# UWB_DWM1000.net
KiCad netlist of a schematic drawn in Altium Designer
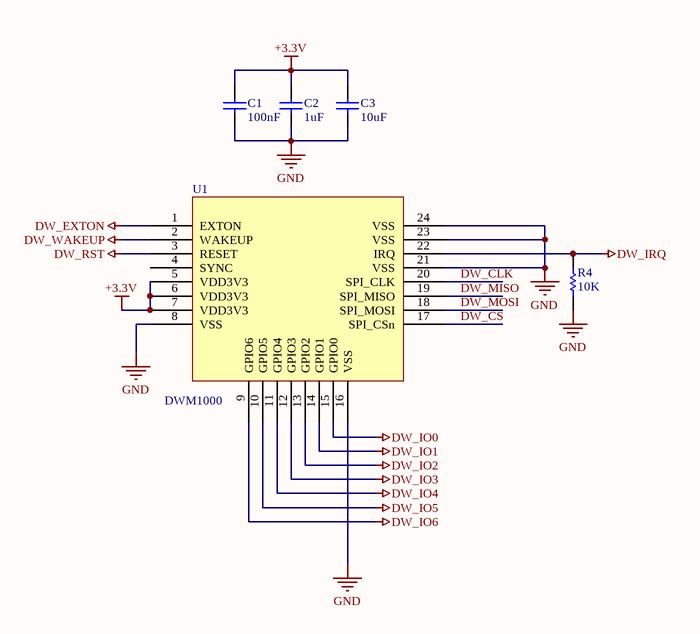
[diagram p0: UWB_DWM1000.SchDoc]

(export (version "E")
  (design (tool "Eeschema 10.0.6"))
  (components
    (comp (ref "C1")
      (value "100nF")
      (footprint "CAPC1608N")
      (description "Capacitor")
      (fields (field (name "Comment") "Cap") (field (name "PUBLISHER") "Altium Limited"))
      (libsource (lib "Leo") (part "Cap"))
    )
    (comp (ref "C2")
      (value "1uF")
      (footprint "CAPC1608N")
      (description "Capacitor")
      (fields (field (name "Comment") "Cap") (field (name "PUBLISHER") "Altium Limited"))
      (libsource (lib "Leo") (part "Cap"))
    )
    (comp (ref "C3")
      (value "10uF")
      (footprint "CAPC1608N")
      (description "Capacitor")
      (fields (field (name "Comment") "Cap") (field (name "PUBLISHER") "Altium Limited"))
      (libsource (lib "Leo") (part "Cap"))
    )
    (comp (ref "R4")
      (value "10K")
      (footprint "RESC1608N")
      (description "Resistor")
      (fields (field (name "Comment") "Res1") (field (name "PUBLISHER") "Altium Limited"))
      (libsource (lib "Leo") (part "Res1"))
    )
    (comp (ref "U1")
      (value "DWM1000")
      (footprint "DWM1000")
      (description "MOD IEEE802.15.4-2011 UWB TXRX")
      (fields (field (name "MANUFACTURER") "Decawave Limited"))
      (libsource (lib "Leo") (part "DWM1000"))
    )
  )
  (nets
    (net (code "1") (name "+3.3V") (class "Default")
      (node (ref "C1") (pin "1") (pinfunction "1_1") (pintype "passive"))
      (node (ref "C2") (pin "1") (pinfunction "1_1") (pintype "passive"))
      (node (ref "C3") (pin "1") (pinfunction "1_1") (pintype "passive"))
      (node (ref "U1") (pin "5") (pinfunction "VDD3V3_5") (pintype "passive"))
      (node (ref "U1") (pin "6") (pinfunction "VDD3V3_6") (pintype "passive"))
      (node (ref "U1") (pin "7") (pinfunction "VDD3V3_7") (pintype "passive"))
    )
    (net (code "2") (name "/DW_CLK") (class "Default")
      (node (ref "U1") (pin "20") (pinfunction "SPI_CLK_20") (pintype "passive"))
    )
    (net (code "3") (name "/DW_CS") (class "Default")
      (node (ref "U1") (pin "17") (pinfunction "SPI_CSn_17") (pintype "passive"))
    )
    (net (code "4") (name "/DW_MISO") (class "Default")
      (node (ref "U1") (pin "19") (pinfunction "SPI_MISO_19") (pintype "passive"))
    )
    (net (code "5") (name "/DW_MOSI") (class "Default")
      (node (ref "U1") (pin "18") (pinfunction "SPI_MOSI_18") (pintype "passive"))
    )
    (net (code "6") (name "DW_EXTON") (class "Default")
      (node (ref "U1") (pin "1") (pinfunction "EXTON_1") (pintype "passive"))
    )
    (net (code "7") (name "DW_IO0") (class "Default")
      (node (ref "U1") (pin "15") (pinfunction "GPIO0_15") (pintype "passive"))
    )
    (net (code "8") (name "DW_IO1") (class "Default")
      (node (ref "U1") (pin "14") (pinfunction "GPIO1_14") (pintype "passive"))
    )
    (net (code "9") (name "DW_IO2") (class "Default")
      (node (ref "U1") (pin "13") (pinfunction "GPIO2_13") (pintype "passive"))
    )
    (net (code "10") (name "DW_IO3") (class "Default")
      (node (ref "U1") (pin "12") (pinfunction "GPIO3_12") (pintype "passive"))
    )
    (net (code "11") (name "DW_IO4") (class "Default")
      (node (ref "U1") (pin "11") (pinfunction "GPIO4_11") (pintype "passive"))
    )
    (net (code "12") (name "DW_IO5") (class "Default")
      (node (ref "U1") (pin "10") (pinfunction "GPIO5_10") (pintype "passive"))
    )
    (net (code "13") (name "DW_IO6") (class "Default")
      (node (ref "U1") (pin "9") (pinfunction "GPIO6_9") (pintype "passive"))
    )
    (net (code "14") (name "DW_IRQ") (class "Default")
      (node (ref "R4") (pin "2") (pinfunction "2_2") (pintype "passive"))
      (node (ref "U1") (pin "22") (pinfunction "IRQ_22") (pintype "passive"))
    )
    (net (code "15") (name "DW_RST") (class "Default")
      (node (ref "U1") (pin "3") (pinfunction "RESET_3") (pintype "passive"))
    )
    (net (code "16") (name "DW_WAKEUP") (class "Default")
      (node (ref "U1") (pin "2") (pinfunction "WAKEUP_2") (pintype "passive"))
    )
    (net (code "17") (name "GND") (class "Default")
      (node (ref "C1") (pin "2") (pinfunction "2_2") (pintype "passive"))
      (node (ref "C2") (pin "2") (pinfunction "2_2") (pintype "passive"))
      (node (ref "C3") (pin "2") (pinfunction "2_2") (pintype "passive"))
      (node (ref "R4") (pin "1") (pinfunction "1_1") (pintype "passive"))
      (node (ref "U1") (pin "16") (pinfunction "VSS_16") (pintype "passive"))
      (node (ref "U1") (pin "21") (pinfunction "VSS_21") (pintype "passive"))
      (node (ref "U1") (pin "23") (pinfunction "VSS_23") (pintype "passive"))
      (node (ref "U1") (pin "24") (pinfunction "VSS_24") (pintype "passive"))
      (node (ref "U1") (pin "8") (pinfunction "VSS_8") (pintype "passive"))
    )
    (net (code "18") (name "unconnected-(U1-SYNC-Pad4)") (class "Default")
      (node (ref "U1") (pin "4") (pinfunction "SYNC_4") (pintype "passive"))
    )
  )
)
